# xenium-programmer-chip.net
KiCad netlist of a schematic drawn in EAGLE
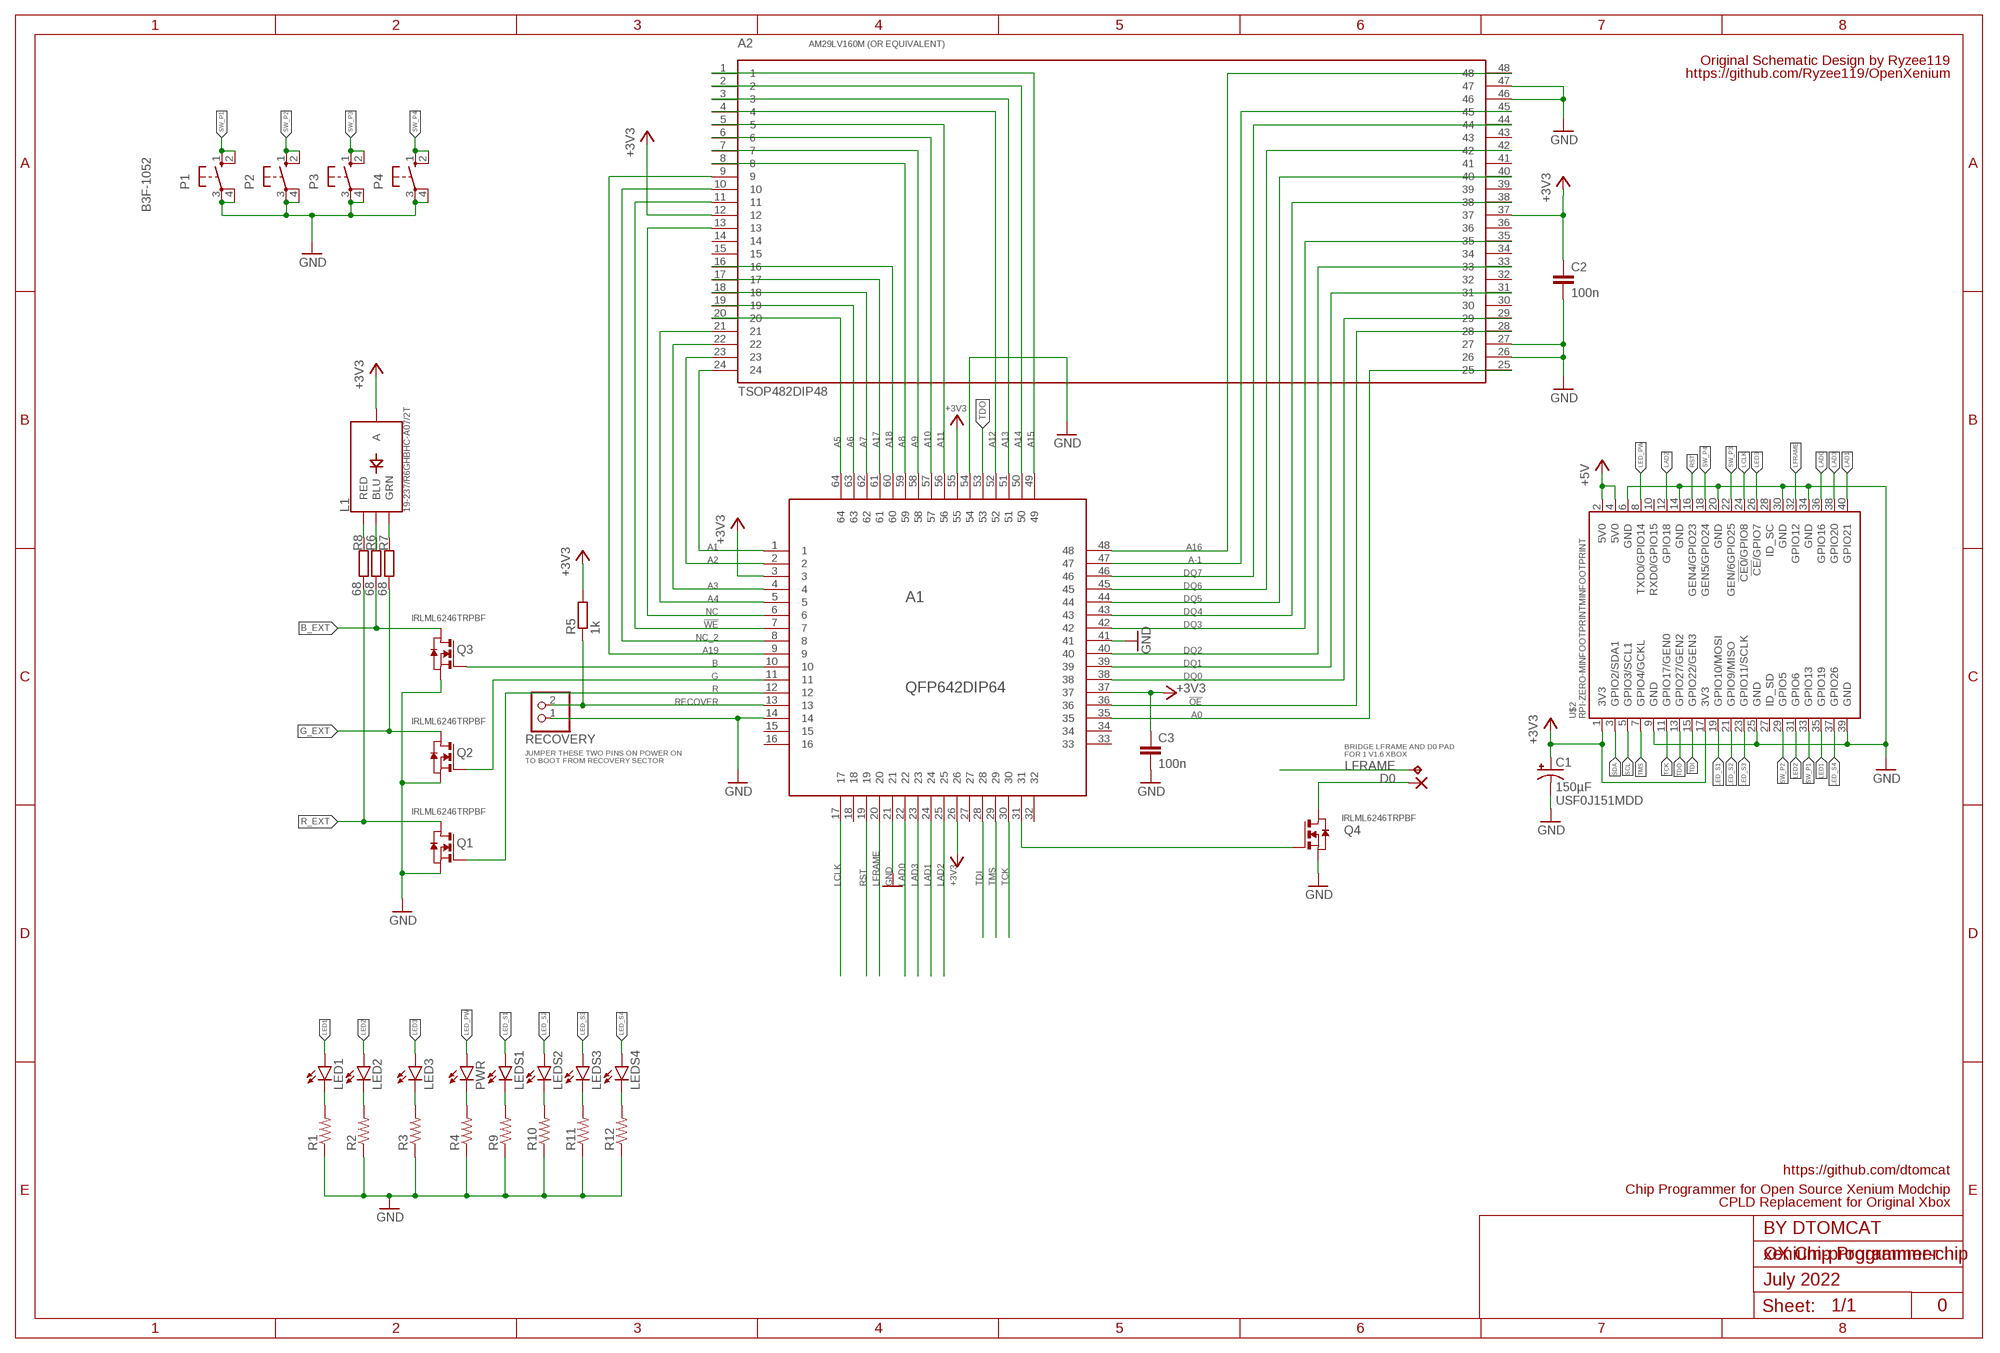
[diagram p0: schematic, sheet 1]

(export (version "E")
  (design (tool "Eeschema 10.0.6"))
  (components
    (comp (ref "A1")
      (value "QFP642DIP64")
      (footprint "eagle-import:QFP642DIP64")
      (libsource (lib "eagle-import") (part "QFP642DIP64"))
    )
    (comp (ref "A2")
      (value "TSOP482DIP48")
      (footprint "eagle-import:TSOP482DIP48")
      (libsource (lib "eagle-import") (part "TSOP482DIP48"))
    )
    (comp (ref "C1")
      (value "150µF")
      (footprint "eagle-import:E3,5-8")
      (libsource (lib "eagle-import") (part "CPOL-USE3.5-8"))
    )
    (comp (ref "C2")
      (value "100n")
      (footprint "eagle-import:C0603")
      (libsource (lib "eagle-import") (part "C-EUC0603"))
    )
    (comp (ref "C3")
      (value "100n")
      (footprint "eagle-import:C0603")
      (libsource (lib "eagle-import") (part "C-EUC0603"))
    )
    (comp (ref "D0")
      (value "SMD2")
      (footprint "eagle-import:SMD1,27-2,54")
      (libsource (lib "eagle-import") (part "SMD2"))
    )
    (comp (ref "L1")
      (value "19-237/R6GHBHC-A07/2T")
      (footprint "eagle-import:4-SMD-R6GHBHC")
      (libsource (lib "eagle-import") (part "19-237/R6GHBHC-A07/2T"))
    )
    (comp (ref "LED1")
      (value "LEDCHIPLED_1206")
      (footprint "eagle-import:CHIPLED_1206")
      (libsource (lib "eagle-import") (part "LEDCHIPLED_1206"))
    )
    (comp (ref "LED2")
      (value "LEDCHIPLED_1206")
      (footprint "eagle-import:CHIPLED_1206")
      (libsource (lib "eagle-import") (part "LEDCHIPLED_1206"))
    )
    (comp (ref "LED3")
      (value "LEDCHIPLED_1206")
      (footprint "eagle-import:CHIPLED_1206")
      (libsource (lib "eagle-import") (part "LEDCHIPLED_1206"))
    )
    (comp (ref "LEDS1")
      (value "LEDCHIPLED_1206")
      (footprint "eagle-import:CHIPLED_1206")
      (libsource (lib "eagle-import") (part "LEDCHIPLED_1206"))
    )
    (comp (ref "LEDS2")
      (value "LEDCHIPLED_1206")
      (footprint "eagle-import:CHIPLED_1206")
      (libsource (lib "eagle-import") (part "LEDCHIPLED_1206"))
    )
    (comp (ref "LEDS3")
      (value "LEDCHIPLED_1206")
      (footprint "eagle-import:CHIPLED_1206")
      (libsource (lib "eagle-import") (part "LEDCHIPLED_1206"))
    )
    (comp (ref "LEDS4")
      (value "LEDCHIPLED_1206")
      (footprint "eagle-import:CHIPLED_1206")
      (libsource (lib "eagle-import") (part "LEDCHIPLED_1206"))
    )
    (comp (ref "P1")
      (value "B3F-1052")
      (footprint "eagle-import:B3F-10XX")
      (fields (field (name "MF") "Omron"))
      (libsource (lib "eagle-import") (part "B3F-1052"))
    )
    (comp (ref "P2")
      (value "B3F-1052")
      (footprint "eagle-import:B3F-10XX")
      (fields (field (name "MF") "Omron"))
      (libsource (lib "eagle-import") (part "B3F-1052"))
    )
    (comp (ref "P3")
      (value "B3F-1052")
      (footprint "eagle-import:B3F-10XX")
      (fields (field (name "MF") "Omron"))
      (libsource (lib "eagle-import") (part "B3F-1052"))
    )
    (comp (ref "P4")
      (value "B3F-1052")
      (footprint "eagle-import:B3F-10XX")
      (fields (field (name "MF") "Omron"))
      (libsource (lib "eagle-import") (part "B3F-1052"))
    )
    (comp (ref "PWR")
      (value "LEDCHIPLED_1206")
      (footprint "eagle-import:CHIPLED_1206")
      (libsource (lib "eagle-import") (part "LEDCHIPLED_1206"))
    )
    (comp (ref "Q1")
      (value "310mA/60V/1.6Ω")
      (footprint "eagle-import:SOT-23")
      (libsource (lib "eagle-import") (part "NMOSSOT23"))
    )
    (comp (ref "Q2")
      (value "310mA/60V/1.6Ω")
      (footprint "eagle-import:SOT-23")
      (libsource (lib "eagle-import") (part "NMOSSOT23"))
    )
    (comp (ref "Q3")
      (value "310mA/60V/1.6Ω")
      (footprint "eagle-import:SOT-23")
      (libsource (lib "eagle-import") (part "NMOSSOT23"))
    )
    (comp (ref "Q4")
      (value "310mA/60V/1.6Ω")
      (footprint "eagle-import:SOT-23")
      (libsource (lib "eagle-import") (part "NMOSSOT23"))
    )
    (comp (ref "R1")
      (value "R-US_R1206")
      (footprint "eagle-import:R1206")
      (libsource (lib "eagle-import") (part "R-US_R1206"))
    )
    (comp (ref "R2")
      (value "R-US_R1206")
      (footprint "eagle-import:R1206")
      (libsource (lib "eagle-import") (part "R-US_R1206"))
    )
    (comp (ref "R3")
      (value "R-US_R1206")
      (footprint "eagle-import:R1206")
      (libsource (lib "eagle-import") (part "R-US_R1206"))
    )
    (comp (ref "R4")
      (value "R-US_R1206")
      (footprint "eagle-import:R1206")
      (libsource (lib "eagle-import") (part "R-US_R1206"))
    )
    (comp (ref "R5")
      (value "1k")
      (footprint "eagle-import:R0603")
      (libsource (lib "eagle-import") (part "R-EU_R0603"))
    )
    (comp (ref "R6")
      (value "68")
      (footprint "eagle-import:R0603")
      (libsource (lib "eagle-import") (part "R-EU_R0603"))
    )
    (comp (ref "R7")
      (value "68")
      (footprint "eagle-import:R0603")
      (libsource (lib "eagle-import") (part "R-EU_R0603"))
    )
    (comp (ref "R8")
      (value "68")
      (footprint "eagle-import:R0603")
      (libsource (lib "eagle-import") (part "R-EU_R0603"))
    )
    (comp (ref "R9")
      (value "R-US_R1206")
      (footprint "eagle-import:R1206")
      (libsource (lib "eagle-import") (part "R-US_R1206"))
    )
    (comp (ref "R10")
      (value "R-US_R1206")
      (footprint "eagle-import:R1206")
      (libsource (lib "eagle-import") (part "R-US_R1206"))
    )
    (comp (ref "R11")
      (value "R-US_R1206")
      (footprint "eagle-import:R1206")
      (libsource (lib "eagle-import") (part "R-US_R1206"))
    )
    (comp (ref "R12")
      (value "R-US_R1206")
      (footprint "eagle-import:R1206")
      (libsource (lib "eagle-import") (part "R-US_R1206"))
    )
    (comp (ref "RECOVERY")
      (value "PINHD-1X2")
      (footprint "eagle-import:1X02")
      (libsource (lib "eagle-import") (part "PINHD-1X2"))
    )
    (comp (ref "TP1")
      (value "TPTP13SQ")
      (footprint "eagle-import:TP13SQ")
      (libsource (lib "eagle-import") (part "TPTP13SQ"))
    )
    (comp (ref "U$2")
      (value "RPI-ZERO-MINFOOTPRINTMINFOOTPRINT")
      (footprint "eagle-import:RASP_PI_ZERO_MIN")
      (libsource (lib "eagle-import") (part "RPI-ZERO-MINFOOTPRINTMINFOOTPRINT"))
    )
  )
  (nets
    (net (code "1") (name "+3V3") (class "Default")
      (node (ref "A1") (pin "26") (pinfunction "26_26") (pintype "bidirectional"))
      (node (ref "A1") (pin "3") (pinfunction "3_3") (pintype "bidirectional"))
      (node (ref "A1") (pin "37") (pinfunction "37_37") (pintype "bidirectional"))
      (node (ref "A1") (pin "55") (pinfunction "55_55") (pintype "bidirectional"))
      (node (ref "A2") (pin "12") (pinfunction "12_12") (pintype "bidirectional"))
      (node (ref "A2") (pin "37") (pinfunction "37_37") (pintype "bidirectional"))
      (node (ref "C1") (pin "+") (pinfunction "+_+") (pintype "passive"))
      (node (ref "C2") (pin "1") (pinfunction "1_1") (pintype "passive"))
      (node (ref "C3") (pin "1") (pinfunction "1_1") (pintype "passive"))
      (node (ref "L1") (pin "P$2") (pinfunction "A_P$2") (pintype "bidirectional"))
      (node (ref "R5") (pin "2") (pinfunction "2_2") (pintype "passive"))
      (node (ref "U$2") (pin "1") (pinfunction "3V3_1") (pintype "power_in"))
      (node (ref "U$2") (pin "17") (pinfunction "3V3_17") (pintype "power_in"))
    )
    (net (code "2") (name "+5V") (class "Default")
      (node (ref "U$2") (pin "2") (pinfunction "5V0_2") (pintype "power_in"))
      (node (ref "U$2") (pin "4") (pinfunction "5V0_4") (pintype "power_in"))
    )
    (net (code "3") (name "/A-1") (class "Default")
      (node (ref "A1") (pin "47") (pinfunction "47_47") (pintype "bidirectional"))
      (node (ref "A2") (pin "45") (pinfunction "45_45") (pintype "bidirectional"))
    )
    (net (code "4") (name "/A0") (class "Default")
      (node (ref "A1") (pin "35") (pinfunction "35_35") (pintype "bidirectional"))
      (node (ref "A2") (pin "25") (pinfunction "25_25") (pintype "bidirectional"))
    )
    (net (code "5") (name "/A1") (class "Default")
      (node (ref "A1") (pin "1") (pinfunction "1_1") (pintype "bidirectional"))
      (node (ref "A2") (pin "24") (pinfunction "24_24") (pintype "bidirectional"))
    )
    (net (code "6") (name "/A2") (class "Default")
      (node (ref "A1") (pin "2") (pinfunction "2_2") (pintype "bidirectional"))
      (node (ref "A2") (pin "23") (pinfunction "23_23") (pintype "bidirectional"))
    )
    (net (code "7") (name "/A3") (class "Default")
      (node (ref "A1") (pin "4") (pinfunction "4_4") (pintype "bidirectional"))
      (node (ref "A2") (pin "22") (pinfunction "22_22") (pintype "bidirectional"))
    )
    (net (code "8") (name "/A4") (class "Default")
      (node (ref "A1") (pin "5") (pinfunction "5_5") (pintype "bidirectional"))
      (node (ref "A2") (pin "21") (pinfunction "21_21") (pintype "bidirectional"))
    )
    (net (code "9") (name "/A5") (class "Default")
      (node (ref "A1") (pin "64") (pinfunction "64_64") (pintype "bidirectional"))
      (node (ref "A2") (pin "20") (pinfunction "20_20") (pintype "bidirectional"))
    )
    (net (code "10") (name "/A6") (class "Default")
      (node (ref "A1") (pin "63") (pinfunction "63_63") (pintype "bidirectional"))
      (node (ref "A2") (pin "19") (pinfunction "19_19") (pintype "bidirectional"))
    )
    (net (code "11") (name "/A7") (class "Default")
      (node (ref "A1") (pin "62") (pinfunction "62_62") (pintype "bidirectional"))
      (node (ref "A2") (pin "18") (pinfunction "18_18") (pintype "bidirectional"))
    )
    (net (code "12") (name "/A8") (class "Default")
      (node (ref "A1") (pin "59") (pinfunction "59_59") (pintype "bidirectional"))
      (node (ref "A2") (pin "8") (pinfunction "8_8") (pintype "bidirectional"))
    )
    (net (code "13") (name "/A9") (class "Default")
      (node (ref "A1") (pin "58") (pinfunction "58_58") (pintype "bidirectional"))
      (node (ref "A2") (pin "7") (pinfunction "7_7") (pintype "bidirectional"))
    )
    (net (code "14") (name "/A10") (class "Default")
      (node (ref "A1") (pin "57") (pinfunction "57_57") (pintype "bidirectional"))
      (node (ref "A2") (pin "6") (pinfunction "6_6") (pintype "bidirectional"))
    )
    (net (code "15") (name "/A11") (class "Default")
      (node (ref "A1") (pin "56") (pinfunction "56_56") (pintype "bidirectional"))
      (node (ref "A2") (pin "5") (pinfunction "5_5") (pintype "bidirectional"))
    )
    (net (code "16") (name "/A12") (class "Default")
      (node (ref "A1") (pin "52") (pinfunction "52_52") (pintype "bidirectional"))
      (node (ref "A2") (pin "4") (pinfunction "4_4") (pintype "bidirectional"))
    )
    (net (code "17") (name "/A13") (class "Default")
      (node (ref "A1") (pin "51") (pinfunction "51_51") (pintype "bidirectional"))
      (node (ref "A2") (pin "3") (pinfunction "3_3") (pintype "bidirectional"))
    )
    (net (code "18") (name "/A14") (class "Default")
      (node (ref "A1") (pin "50") (pinfunction "50_50") (pintype "bidirectional"))
      (node (ref "A2") (pin "2") (pinfunction "2_2") (pintype "bidirectional"))
    )
    (net (code "19") (name "/A15") (class "Default")
      (node (ref "A1") (pin "49") (pinfunction "49_49") (pintype "bidirectional"))
      (node (ref "A2") (pin "1") (pinfunction "1_1") (pintype "bidirectional"))
    )
    (net (code "20") (name "/A16") (class "Default")
      (node (ref "A1") (pin "48") (pinfunction "48_48") (pintype "bidirectional"))
      (node (ref "A2") (pin "48") (pinfunction "48_48") (pintype "bidirectional"))
    )
    (net (code "21") (name "/A17") (class "Default")
      (node (ref "A1") (pin "61") (pinfunction "61_61") (pintype "bidirectional"))
      (node (ref "A2") (pin "17") (pinfunction "17_17") (pintype "bidirectional"))
    )
    (net (code "22") (name "/A18") (class "Default")
      (node (ref "A1") (pin "60") (pinfunction "60_60") (pintype "bidirectional"))
      (node (ref "A2") (pin "16") (pinfunction "16_16") (pintype "bidirectional"))
    )
    (net (code "23") (name "/A19") (class "Default")
      (node (ref "A1") (pin "9") (pinfunction "9_9") (pintype "bidirectional"))
      (node (ref "A2") (pin "9") (pinfunction "9_9") (pintype "bidirectional"))
    )
    (net (code "24") (name "/B") (class "Default")
      (node (ref "A1") (pin "10") (pinfunction "10_10") (pintype "bidirectional"))
      (node (ref "Q3") (pin "3") (pinfunction "G_3") (pintype "passive"))
    )
    (net (code "25") (name "/DQ0") (class "Default")
      (node (ref "A1") (pin "38") (pinfunction "38_38") (pintype "bidirectional"))
      (node (ref "A2") (pin "29") (pinfunction "29_29") (pintype "bidirectional"))
    )
    (net (code "26") (name "/DQ1") (class "Default")
      (node (ref "A1") (pin "39") (pinfunction "39_39") (pintype "bidirectional"))
      (node (ref "A2") (pin "31") (pinfunction "31_31") (pintype "bidirectional"))
    )
    (net (code "27") (name "/DQ2") (class "Default")
      (node (ref "A1") (pin "40") (pinfunction "40_40") (pintype "bidirectional"))
      (node (ref "A2") (pin "33") (pinfunction "33_33") (pintype "bidirectional"))
    )
    (net (code "28") (name "/DQ3") (class "Default")
      (node (ref "A1") (pin "42") (pinfunction "42_42") (pintype "bidirectional"))
      (node (ref "A2") (pin "35") (pinfunction "35_35") (pintype "bidirectional"))
    )
    (net (code "29") (name "/DQ4") (class "Default")
      (node (ref "A1") (pin "43") (pinfunction "43_43") (pintype "bidirectional"))
      (node (ref "A2") (pin "38") (pinfunction "38_38") (pintype "bidirectional"))
    )
    (net (code "30") (name "/DQ5") (class "Default")
      (node (ref "A1") (pin "44") (pinfunction "44_44") (pintype "bidirectional"))
      (node (ref "A2") (pin "40") (pinfunction "40_40") (pintype "bidirectional"))
    )
    (net (code "31") (name "/DQ6") (class "Default")
      (node (ref "A1") (pin "45") (pinfunction "45_45") (pintype "bidirectional"))
      (node (ref "A2") (pin "42") (pinfunction "42_42") (pintype "bidirectional"))
    )
    (net (code "32") (name "/DQ7") (class "Default")
      (node (ref "A1") (pin "46") (pinfunction "46_46") (pintype "bidirectional"))
      (node (ref "A2") (pin "44") (pinfunction "44_44") (pintype "bidirectional"))
    )
    (net (code "33") (name "/G") (class "Default")
      (node (ref "A1") (pin "11") (pinfunction "11_11") (pintype "bidirectional"))
      (node (ref "Q2") (pin "3") (pinfunction "G_3") (pintype "passive"))
    )
    (net (code "34") (name "/NC") (class "Default")
      (node (ref "A1") (pin "6") (pinfunction "6_6") (pintype "bidirectional"))
      (node (ref "A2") (pin "13") (pinfunction "13_13") (pintype "bidirectional"))
    )
    (net (code "35") (name "/NC_2") (class "Default")
      (node (ref "A1") (pin "8") (pinfunction "8_8") (pintype "bidirectional"))
      (node (ref "A2") (pin "10") (pinfunction "10_10") (pintype "bidirectional"))
    )
    (net (code "36") (name "/R") (class "Default")
      (node (ref "A1") (pin "12") (pinfunction "12_12") (pintype "bidirectional"))
      (node (ref "Q1") (pin "3") (pinfunction "G_3") (pintype "passive"))
    )
    (net (code "37") (name "/RECOVER") (class "Default")
      (node (ref "A1") (pin "13") (pinfunction "13_13") (pintype "bidirectional"))
      (node (ref "R5") (pin "1") (pinfunction "1_1") (pintype "passive"))
      (node (ref "RECOVERY") (pin "2") (pinfunction "2_2") (pintype "passive"))
    )
    (net (code "38") (name "/~{OE}") (class "Default")
      (node (ref "A1") (pin "36") (pinfunction "36_36") (pintype "bidirectional"))
      (node (ref "A2") (pin "28") (pinfunction "28_28") (pintype "bidirectional"))
    )
    (net (code "39") (name "/~{WE}") (class "Default")
      (node (ref "A1") (pin "7") (pinfunction "7_7") (pintype "bidirectional"))
      (node (ref "A2") (pin "11") (pinfunction "11_11") (pintype "bidirectional"))
    )
    (net (code "40") (name "B_EXT") (class "Default")
      (node (ref "Q3") (pin "1") (pinfunction "D_1") (pintype "passive"))
      (node (ref "R6") (pin "2") (pinfunction "2_2") (pintype "passive"))
    )
    (net (code "41") (name "GND") (class "Default")
      (node (ref "A1") (pin "14") (pinfunction "14_14") (pintype "bidirectional"))
      (node (ref "A1") (pin "21") (pinfunction "21_21") (pintype "bidirectional"))
      (node (ref "A1") (pin "41") (pinfunction "41_41") (pintype "bidirectional"))
      (node (ref "A1") (pin "54") (pinfunction "54_54") (pintype "bidirectional"))
      (node (ref "A2") (pin "26") (pinfunction "26_26") (pintype "bidirectional"))
      (node (ref "A2") (pin "27") (pinfunction "27_27") (pintype "bidirectional"))
      (node (ref "A2") (pin "46") (pinfunction "46_46") (pintype "bidirectional"))
      (node (ref "A2") (pin "47") (pinfunction "47_47") (pintype "bidirectional"))
      (node (ref "C1") (pin "-") (pinfunction "-_-") (pintype "passive"))
      (node (ref "C2") (pin "2") (pinfunction "2_2") (pintype "passive"))
      (node (ref "C3") (pin "2") (pinfunction "2_2") (pintype "passive"))
      (node (ref "P1") (pin "3") (pinfunction "P_3") (pintype "passive"))
      (node (ref "P1") (pin "4") (pinfunction "P1_4") (pintype "passive"))
      (node (ref "P2") (pin "3") (pinfunction "P_3") (pintype "passive"))
      (node (ref "P2") (pin "4") (pinfunction "P1_4") (pintype "passive"))
      (node (ref "P3") (pin "3") (pinfunction "P_3") (pintype "passive"))
      (node (ref "P3") (pin "4") (pinfunction "P1_4") (pintype "passive"))
      (node (ref "P4") (pin "3") (pinfunction "P_3") (pintype "passive"))
      (node (ref "P4") (pin "4") (pinfunction "P1_4") (pintype "passive"))
      (node (ref "Q1") (pin "2") (pinfunction "S_2") (pintype "passive"))
      (node (ref "Q2") (pin "2") (pinfunction "S_2") (pintype "passive"))
      (node (ref "Q3") (pin "2") (pinfunction "S_2") (pintype "passive"))
      (node (ref "Q4") (pin "2") (pinfunction "S_2") (pintype "passive"))
      (node (ref "R1") (pin "1") (pinfunction "1_1") (pintype "passive"))
      (node (ref "R10") (pin "1") (pinfunction "1_1") (pintype "passive"))
      (node (ref "R11") (pin "1") (pinfunction "1_1") (pintype "passive"))
      (node (ref "R12") (pin "1") (pinfunction "1_1") (pintype "passive"))
      (node (ref "R2") (pin "1") (pinfunction "1_1") (pintype "passive"))
      (node (ref "R3") (pin "1") (pinfunction "1_1") (pintype "passive"))
      (node (ref "R4") (pin "1") (pinfunction "1_1") (pintype "passive"))
      (node (ref "R9") (pin "1") (pinfunction "1_1") (pintype "passive"))
      (node (ref "RECOVERY") (pin "1") (pinfunction "1_1") (pintype "passive"))
      (node (ref "U$2") (pin "14") (pinfunction "GND_14") (pintype "power_in"))
      (node (ref "U$2") (pin "20") (pinfunction "GND_20") (pintype "power_in"))
      (node (ref "U$2") (pin "25") (pinfunction "GND_25") (pintype "power_in"))
      (node (ref "U$2") (pin "30") (pinfunction "GND_30") (pintype "power_in"))
      (node (ref "U$2") (pin "34") (pinfunction "GND_34") (pintype "power_in"))
      (node (ref "U$2") (pin "39") (pinfunction "GND_39") (pintype "power_in"))
      (node (ref "U$2") (pin "6") (pinfunction "GND_6") (pintype "power_in"))
      (node (ref "U$2") (pin "9") (pinfunction "GND_9") (pintype "power_in"))
    )
    (net (code "42") (name "G_EXT") (class "Default")
      (node (ref "Q2") (pin "1") (pinfunction "D_1") (pintype "passive"))
      (node (ref "R7") (pin "2") (pinfunction "2_2") (pintype "passive"))
    )
    (net (code "43") (name "LAD0") (class "Default")
      (node (ref "A1") (pin "22") (pinfunction "22_22") (pintype "bidirectional"))
      (node (ref "U$2") (pin "36") (pinfunction "GPIO16_36") (pintype "bidirectional"))
    )
    (net (code "44") (name "LAD1") (class "Default")
      (node (ref "A1") (pin "24") (pinfunction "24_24") (pintype "bidirectional"))
      (node (ref "U$2") (pin "40") (pinfunction "GPIO21_40") (pintype "bidirectional"))
    )
    (net (code "45") (name "LAD2") (class "Default")
      (node (ref "A1") (pin "25") (pinfunction "25_25") (pintype "bidirectional"))
      (node (ref "U$2") (pin "12") (pinfunction "GPIO18_12") (pintype "bidirectional"))
    )
    (net (code "46") (name "LAD3") (class "Default")
      (node (ref "A1") (pin "23") (pinfunction "23_23") (pintype "bidirectional"))
      (node (ref "U$2") (pin "38") (pinfunction "GPIO20_38") (pintype "bidirectional"))
    )
    (net (code "47") (name "LCLK") (class "Default")
      (node (ref "A1") (pin "17") (pinfunction "17_17") (pintype "bidirectional"))
      (node (ref "U$2") (pin "24") (pinfunction "~{CE0}/GPIO8_24") (pintype "bidirectional"))
    )
    (net (code "48") (name "LED1") (class "Default")
      (node (ref "LED1") (pin "A") (pinfunction "A_A") (pintype "passive"))
      (node (ref "U$2") (pin "35") (pinfunction "GPIO19_35") (pintype "bidirectional"))
    )
    (net (code "49") (name "LED2") (class "Default")
      (node (ref "LED2") (pin "A") (pinfunction "A_A") (pintype "passive"))
      (node (ref "U$2") (pin "31") (pinfunction "GPIO6_31") (pintype "bidirectional"))
    )
    (net (code "50") (name "LED3") (class "Default")
      (node (ref "LED3") (pin "A") (pinfunction "A_A") (pintype "passive"))
      (node (ref "U$2") (pin "26") (pinfunction "~{CE}/GPIO7_26") (pintype "bidirectional"))
    )
    (net (code "51") (name "LED_PW") (class "Default")
      (node (ref "PWR") (pin "A") (pinfunction "A_A") (pintype "passive"))
      (node (ref "U$2") (pin "8") (pinfunction "TXD0/GPIO14_8") (pintype "bidirectional"))
    )
    (net (code "52") (name "LED_S1") (class "Default")
      (node (ref "LEDS1") (pin "A") (pinfunction "A_A") (pintype "passive"))
      (node (ref "U$2") (pin "19") (pinfunction "GPIO10/MOSI_19") (pintype "bidirectional"))
    )
    (net (code "53") (name "LED_S2") (class "Default")
      (node (ref "LEDS2") (pin "A") (pinfunction "A_A") (pintype "passive"))
      (node (ref "U$2") (pin "21") (pinfunction "GPIO9/MISO_21") (pintype "bidirectional"))
    )
    (net (code "54") (name "LED_S3") (class "Default")
      (node (ref "LEDS3") (pin "A") (pinfunction "A_A") (pintype "passive"))
      (node (ref "U$2") (pin "23") (pinfunction "GPIO11/SCLK_23") (pintype "bidirectional"))
    )
    (net (code "55") (name "LED_S4") (class "Default")
      (node (ref "LEDS4") (pin "A") (pinfunction "A_A") (pintype "passive"))
      (node (ref "U$2") (pin "37") (pinfunction "GPIO26_37") (pintype "bidirectional"))
    )
    (net (code "56") (name "LFRAME") (class "Default")
      (node (ref "A1") (pin "20") (pinfunction "20_20") (pintype "bidirectional"))
      (node (ref "TP1") (pin "TP") (pinfunction "TP_TP") (pintype "input"))
      (node (ref "U$2") (pin "32") (pinfunction "GPIO12_32") (pintype "bidirectional"))
    )
    (net (code "57") (name "Net-(D0-P)") (class "Default")
      (node (ref "D0") (pin "1") (pinfunction "P_1") (pintype "passive"))
      (node (ref "Q4") (pin "1") (pinfunction "D_1") (pintype "passive"))
    )
    (net (code "58") (name "Net-(L1-BLU)") (class "Default")
      (node (ref "L1") (pin "P$4") (pinfunction "BLU_P$4") (pintype "bidirectional"))
      (node (ref "R6") (pin "1") (pinfunction "1_1") (pintype "passive"))
    )
    (net (code "59") (name "Net-(L1-GRN)") (class "Default")
      (node (ref "L1") (pin "P$3") (pinfunction "GRN_P$3") (pintype "bidirectional"))
      (node (ref "R7") (pin "1") (pinfunction "1_1") (pintype "passive"))
    )
    (net (code "60") (name "Net-(L1-RED)") (class "Default")
      (node (ref "L1") (pin "P$1") (pinfunction "RED_P$1") (pintype "bidirectional"))
      (node (ref "R8") (pin "1") (pinfunction "1_1") (pintype "passive"))
    )
    (net (code "61") (name "Net-(LED1-PadC)") (class "Default")
      (node (ref "LED1") (pin "C") (pinfunction "C_C") (pintype "passive"))
      (node (ref "R1") (pin "2") (pinfunction "2_2") (pintype "passive"))
    )
    (net (code "62") (name "Net-(LED2-PadC)") (class "Default")
      (node (ref "LED2") (pin "C") (pinfunction "C_C") (pintype "passive"))
      (node (ref "R2") (pin "2") (pinfunction "2_2") (pintype "passive"))
    )
    (net (code "63") (name "Net-(LED3-PadC)") (class "Default")
      (node (ref "LED3") (pin "C") (pinfunction "C_C") (pintype "passive"))
      (node (ref "R3") (pin "2") (pinfunction "2_2") (pintype "passive"))
    )
    (net (code "64") (name "Net-(LEDS1-PadC)") (class "Default")
      (node (ref "LEDS1") (pin "C") (pinfunction "C_C") (pintype "passive"))
      (node (ref "R9") (pin "2") (pinfunction "2_2") (pintype "passive"))
    )
    (net (code "65") (name "Net-(LEDS2-PadC)") (class "Default")
      (node (ref "LEDS2") (pin "C") (pinfunction "C_C") (pintype "passive"))
      (node (ref "R10") (pin "2") (pinfunction "2_2") (pintype "passive"))
    )
    (net (code "66") (name "Net-(LEDS3-PadC)") (class "Default")
      (node (ref "LEDS3") (pin "C") (pinfunction "C_C") (pintype "passive"))
      (node (ref "R11") (pin "2") (pinfunction "2_2") (pintype "passive"))
    )
    (net (code "67") (name "Net-(LEDS4-PadC)") (class "Default")
      (node (ref "LEDS4") (pin "C") (pinfunction "C_C") (pintype "passive"))
      (node (ref "R12") (pin "2") (pinfunction "2_2") (pintype "passive"))
    )
    (net (code "68") (name "Net-(PWR-PadC)") (class "Default")
      (node (ref "PWR") (pin "C") (pinfunction "C_C") (pintype "passive"))
      (node (ref "R4") (pin "2") (pinfunction "2_2") (pintype "passive"))
    )
    (net (code "69") (name "Net-(Q4-G)") (class "Default")
      (node (ref "A1") (pin "31") (pinfunction "31_31") (pintype "bidirectional"))
      (node (ref "Q4") (pin "3") (pinfunction "G_3") (pintype "passive"))
    )
    (net (code "70") (name "RST") (class "Default")
      (node (ref "A1") (pin "19") (pinfunction "19_19") (pintype "bidirectional"))
      (node (ref "U$2") (pin "16") (pinfunction "GEN4/GPIO23_16") (pintype "bidirectional"))
    )
    (net (code "71") (name "R_EXT") (class "Default")
      (node (ref "Q1") (pin "1") (pinfunction "D_1") (pintype "passive"))
      (node (ref "R8") (pin "2") (pinfunction "2_2") (pintype "passive"))
    )
    (net (code "72") (name "SCL") (class "Default")
      (node (ref "U$2") (pin "5") (pinfunction "GPIO3/SCL1_5") (pintype "bidirectional"))
    )
    (net (code "73") (name "SDA") (class "Default")
      (node (ref "U$2") (pin "3") (pinfunction "GPIO2/SDA1_3") (pintype "bidirectional"))
    )
    (net (code "74") (name "SW_P1") (class "Default")
      (node (ref "P1") (pin "1") (pinfunction "S_1") (pintype "passive"))
      (node (ref "P1") (pin "2") (pinfunction "S1_2") (pintype "passive"))
      (node (ref "U$2") (pin "33") (pinfunction "GPIO13_33") (pintype "bidirectional"))
    )
    (net (code "75") (name "SW_P2") (class "Default")
      (node (ref "P2") (pin "1") (pinfunction "S_1") (pintype "passive"))
      (node (ref "P2") (pin "2") (pinfunction "S1_2") (pintype "passive"))
      (node (ref "U$2") (pin "29") (pinfunction "GPIO5_29") (pintype "bidirectional"))
    )
    (net (code "76") (name "SW_P3") (class "Default")
      (node (ref "P3") (pin "1") (pinfunction "S_1") (pintype "passive"))
      (node (ref "P3") (pin "2") (pinfunction "S1_2") (pintype "passive"))
      (node (ref "U$2") (pin "22") (pinfunction "GEN/6GPIO25_22") (pintype "bidirectional"))
    )
    (net (code "77") (name "SW_P4") (class "Default")
      (node (ref "P4") (pin "1") (pinfunction "S_1") (pintype "passive"))
      (node (ref "P4") (pin "2") (pinfunction "S1_2") (pintype "passive"))
      (node (ref "U$2") (pin "18") (pinfunction "GEN5/GPIO24_18") (pintype "bidirectional"))
    )
    (net (code "78") (name "TCK") (class "Default")
      (node (ref "A1") (pin "30") (pinfunction "30_30") (pintype "bidirectional"))
      (node (ref "U$2") (pin "11") (pinfunction "GPIO17/GEN0_11") (pintype "bidirectional"))
    )
    (net (code "79") (name "TDI") (class "Default")
      (node (ref "A1") (pin "28") (pinfunction "28_28") (pintype "bidirectional"))
      (node (ref "U$2") (pin "15") (pinfunction "GPIO22/GEN3_15") (pintype "bidirectional"))
    )
    (net (code "80") (name "TDO") (class "Default")
      (node (ref "A1") (pin "53") (pinfunction "53_53") (pintype "bidirectional"))
      (node (ref "U$2") (pin "13") (pinfunction "GPIO27/GEN2_13") (pintype "bidirectional"))
    )
    (net (code "81") (name "TMS") (class "Default")
      (node (ref "A1") (pin "29") (pinfunction "29_29") (pintype "bidirectional"))
      (node (ref "U$2") (pin "7") (pinfunction "GPIO4/GCKL_7") (pintype "bidirectional"))
    )
    (net (code "82") (name "unconnected-(A1-Pad15)") (class "Default")
      (node (ref "A1") (pin "15") (pinfunction "15_15") (pintype "bidirectional"))
    )
    (net (code "83") (name "unconnected-(A1-Pad16)") (class "Default")
      (node (ref "A1") (pin "16") (pinfunction "16_16") (pintype "bidirectional"))
    )
    (net (code "84") (name "unconnected-(A1-Pad18)") (class "Default")
      (node (ref "A1") (pin "18") (pinfunction "18_18") (pintype "bidirectional"))
    )
    (net (code "85") (name "unconnected-(A1-Pad27)") (class "Default")
      (node (ref "A1") (pin "27") (pinfunction "27_27") (pintype "bidirectional"))
    )
    (net (code "86") (name "unconnected-(A1-Pad32)") (class "Default")
      (node (ref "A1") (pin "32") (pinfunction "32_32") (pintype "bidirectional"))
    )
    (net (code "87") (name "unconnected-(A1-Pad33)") (class "Default")
      (node (ref "A1") (pin "33") (pinfunction "33_33") (pintype "bidirectional"))
    )
    (net (code "88") (name "unconnected-(A1-Pad34)") (class "Default")
      (node (ref "A1") (pin "34") (pinfunction "34_34") (pintype "bidirectional"))
    )
    (net (code "89") (name "unconnected-(A2-Pad14)") (class "Default")
      (node (ref "A2") (pin "14") (pinfunction "14_14") (pintype "bidirectional"))
    )
    (net (code "90") (name "unconnected-(A2-Pad15)") (class "Default")
      (node (ref "A2") (pin "15") (pinfunction "15_15") (pintype "bidirectional"))
    )
    (net (code "91") (name "unconnected-(A2-Pad30)") (class "Default")
      (node (ref "A2") (pin "30") (pinfunction "30_30") (pintype "bidirectional"))
    )
    (net (code "92") (name "unconnected-(A2-Pad32)") (class "Default")
      (node (ref "A2") (pin "32") (pinfunction "32_32") (pintype "bidirectional"))
    )
    (net (code "93") (name "unconnected-(A2-Pad34)") (class "Default")
      (node (ref "A2") (pin "34") (pinfunction "34_34") (pintype "bidirectional"))
    )
    (net (code "94") (name "unconnected-(A2-Pad36)") (class "Default")
      (node (ref "A2") (pin "36") (pinfunction "36_36") (pintype "bidirectional"))
    )
    (net (code "95") (name "unconnected-(A2-Pad39)") (class "Default")
      (node (ref "A2") (pin "39") (pinfunction "39_39") (pintype "bidirectional"))
    )
    (net (code "96") (name "unconnected-(A2-Pad41)") (class "Default")
      (node (ref "A2") (pin "41") (pinfunction "41_41") (pintype "bidirectional"))
    )
    (net (code "97") (name "unconnected-(A2-Pad43)") (class "Default")
      (node (ref "A2") (pin "43") (pinfunction "43_43") (pintype "bidirectional"))
    )
    (net (code "98") (name "unconnected-(U$2-ID_SC-Pad28)") (class "Default")
      (node (ref "U$2") (pin "28") (pinfunction "ID_SC_28") (pintype "bidirectional"))
    )
    (net (code "99") (name "unconnected-(U$2-ID_SD-Pad27)") (class "Default")
      (node (ref "U$2") (pin "27") (pinfunction "ID_SD_27") (pintype "bidirectional"))
    )
    (net (code "100") (name "unconnected-(U$2-RXD0{slash}GPIO15-Pad10)") (class "Default")
      (node (ref "U$2") (pin "10") (pinfunction "RXD0/GPIO15_10") (pintype "bidirectional"))
    )
  )
)
